# Sheet3.net
KiCad netlist of a schematic drawn in Altium Designer
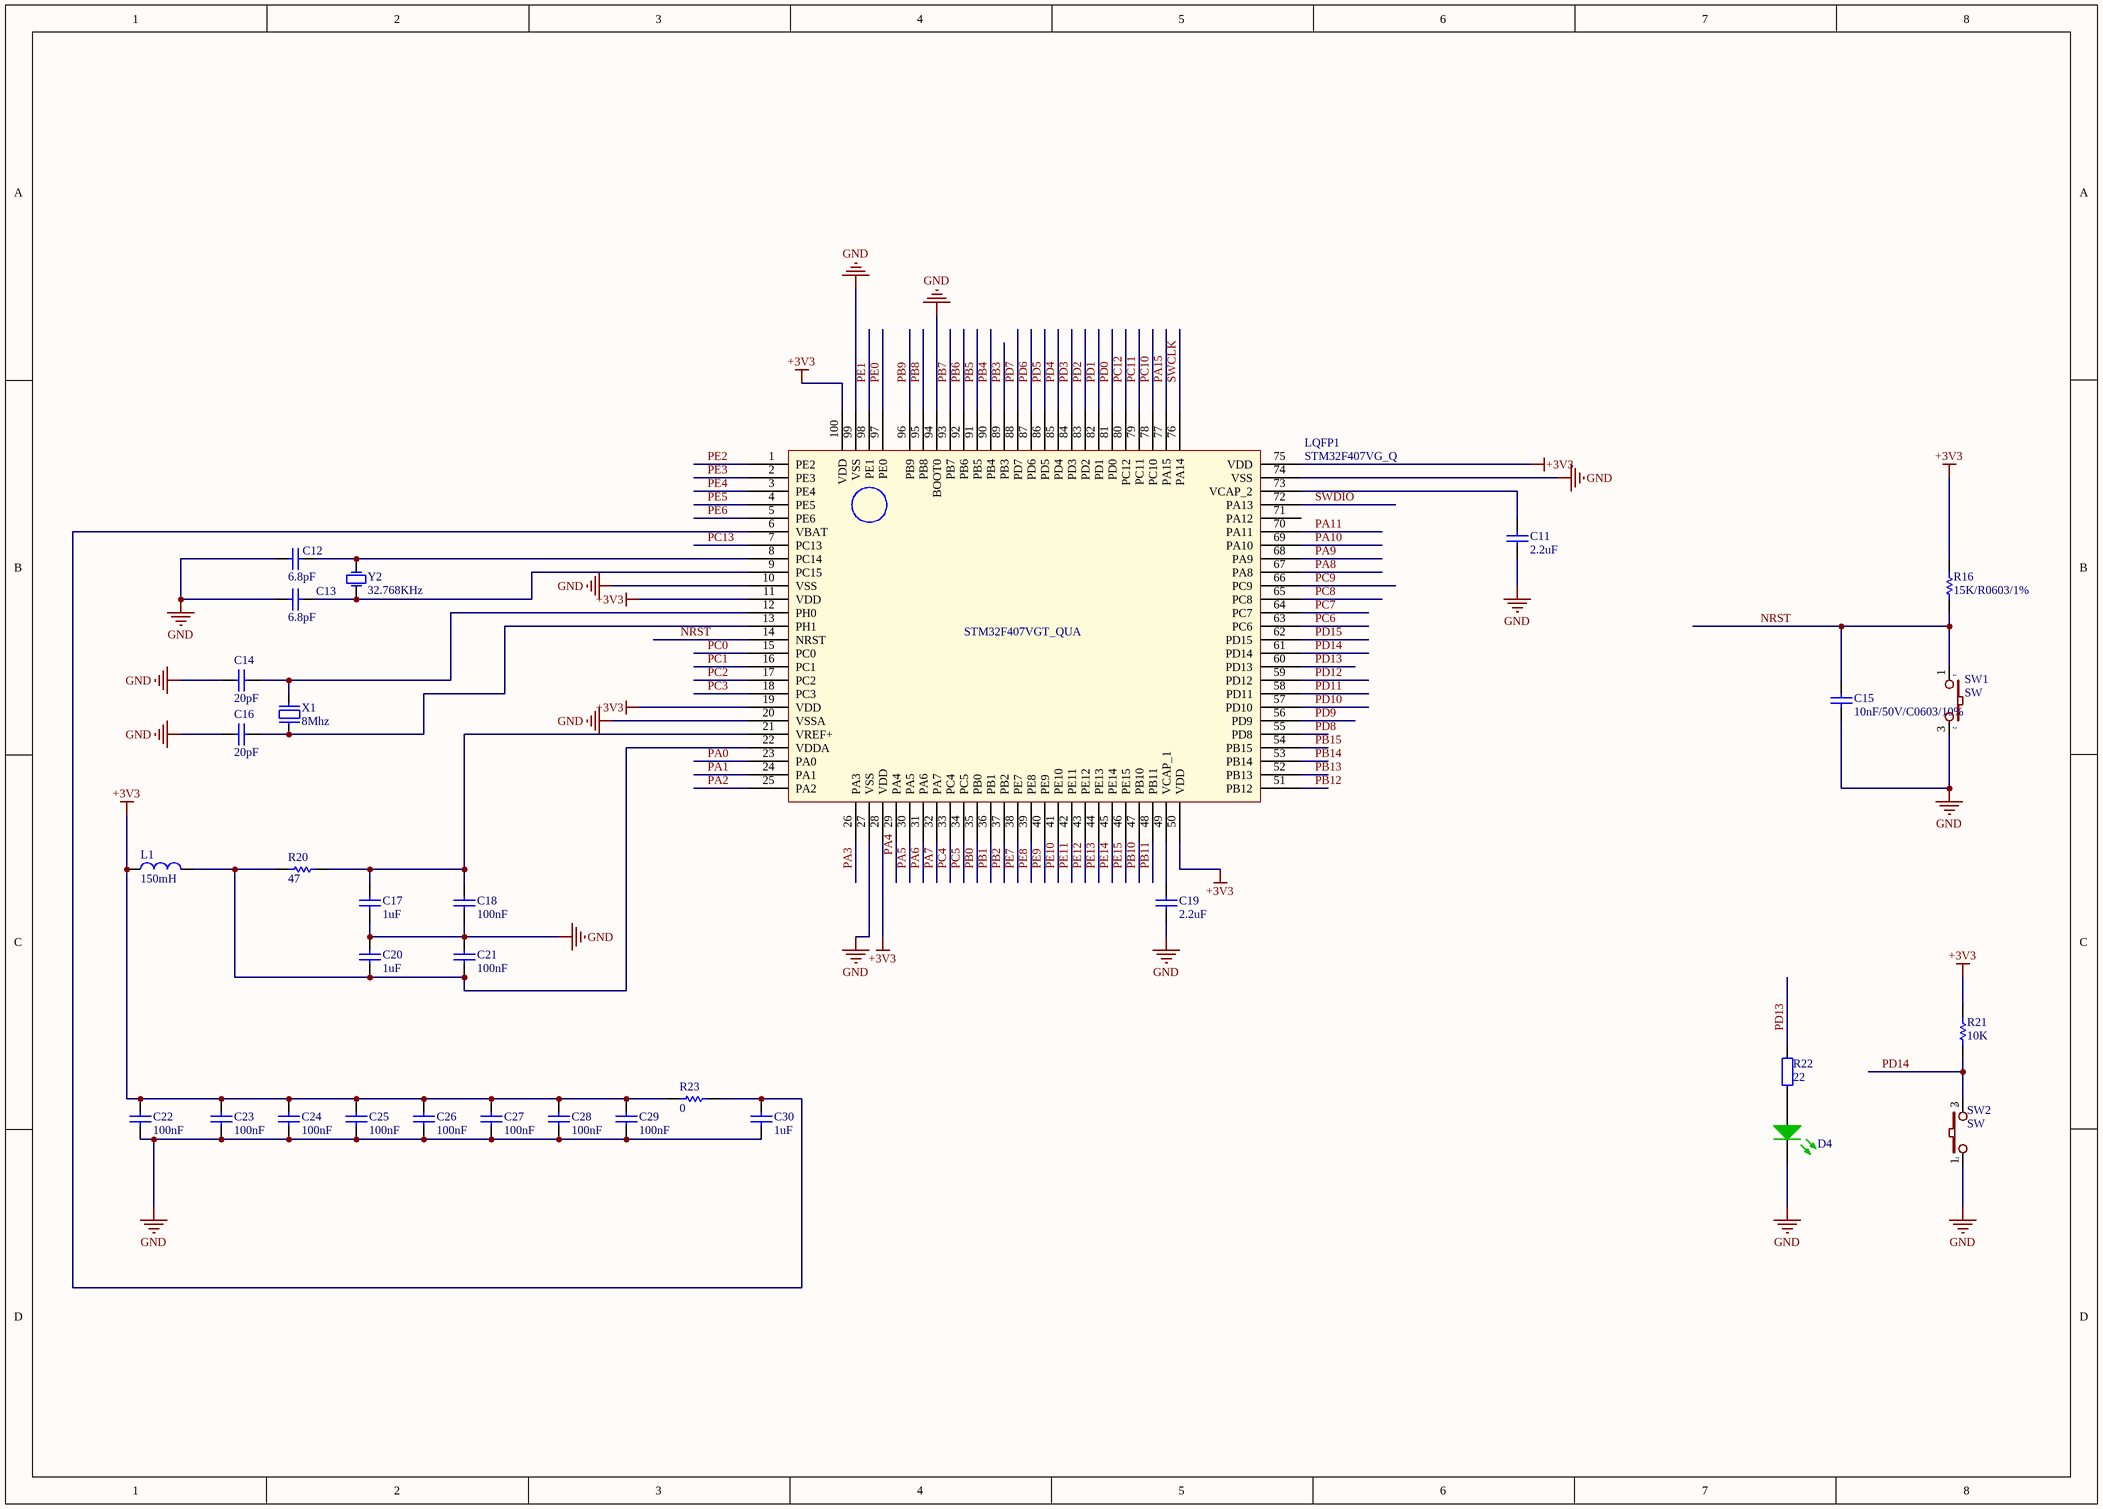
[diagram p0: Sheet3.SchDoc]

(export (version "E")
  (design (tool "Eeschema 10.0.6"))
  (components
    (comp (ref "C11")
      (value "2.2uF")
      (footprint "Cap Ceramic 0805 SMD")
      (description "CAP CER 22PF 50V NP0 0603")
      (fields
        (field (name "MANUFACTURER") "Kemet")
        (field (name "MANUFACTURER PART NUMBER") "C0603C220K5GACTU")
      )
      (libsource (lib "lpson") (part "22pF/50V/C0603/10%"))
    )
    (comp (ref "C12")
      (value "6.8pF")
      (footprint "Cap Ceramic 0805 SMD")
      (description "CAP CER 22PF 50V NP0 0603")
      (fields
        (field (name "MANUFACTURER") "Kemet")
        (field (name "MANUFACTURER PART NUMBER") "C0603C220K5GACTU")
      )
      (libsource (lib "lpson") (part "22pF/50V/C0603/10%"))
    )
    (comp (ref "C13")
      (value "6.8pF")
      (footprint "Cap Ceramic 0805 SMD")
      (description "CAP CER 22PF 50V NP0 0603")
      (fields
        (field (name "MANUFACTURER") "Kemet")
        (field (name "MANUFACTURER PART NUMBER") "C0603C220K5GACTU")
      )
      (libsource (lib "lpson") (part "22pF/50V/C0603/10%"))
    )
    (comp (ref "C14")
      (value "20pF")
      (footprint "Cap Ceramic 0805 SMD")
      (description "CAP CER 22PF 50V NP0 0603")
      (fields
        (field (name "MANUFACTURER") "Kemet")
        (field (name "MANUFACTURER PART NUMBER") "C0603C220K5GACTU")
      )
      (libsource (lib "lpson") (part "22pF/50V/C0603/10%"))
    )
    (comp (ref "C15")
      (value "10nF/50V/C0603/10%")
      (footprint "Cap Ceramic 0805 SMD")
      (description "CAP CER 10000PF 50V X7R 0603")
      (fields
        (field (name "MANUFACTURER") "Murata Electronics North America")
        (field (name "MANUFACTURER PART NUMBER") "GRM188R71H103KA01D")
      )
      (libsource (lib "lpson") (part "10nF/50V/C0603/10%_1"))
    )
    (comp (ref "C16")
      (value "20pF")
      (footprint "Cap Ceramic 0805 SMD")
      (description "CAP CER 22PF 50V NP0 0603")
      (fields
        (field (name "MANUFACTURER") "Kemet")
        (field (name "MANUFACTURER PART NUMBER") "C0603C220K5GACTU")
      )
      (libsource (lib "lpson") (part "22pF/50V/C0603/10%"))
    )
    (comp (ref "C17")
      (value "1uF")
      (footprint "Cap Ceramic 0805 SMD")
      (description "CAP CER 22PF 50V NP0 0603")
      (fields
        (field (name "MANUFACTURER") "Kemet")
        (field (name "MANUFACTURER PART NUMBER") "C0603C220K5GACTU")
      )
      (libsource (lib "lpson") (part "22pF/50V/C0603/10%"))
    )
    (comp (ref "C18")
      (value "100nF")
      (footprint "Cap Ceramic 0805 SMD")
      (description "CAP CER 22PF 50V NP0 0603")
      (fields
        (field (name "MANUFACTURER") "Kemet")
        (field (name "MANUFACTURER PART NUMBER") "C0603C220K5GACTU")
      )
      (libsource (lib "lpson") (part "22pF/50V/C0603/10%"))
    )
    (comp (ref "C19")
      (value "2.2uF")
      (footprint "Cap Ceramic 0805 SMD")
      (description "CAP CER 22PF 50V NP0 0603")
      (fields
        (field (name "MANUFACTURER") "Kemet")
        (field (name "MANUFACTURER PART NUMBER") "C0603C220K5GACTU")
      )
      (libsource (lib "lpson") (part "22pF/50V/C0603/10%"))
    )
    (comp (ref "C20")
      (value "1uF")
      (footprint "Cap Ceramic 0805 SMD")
      (description "CAP CER 22PF 50V NP0 0603")
      (fields
        (field (name "MANUFACTURER") "Kemet")
        (field (name "MANUFACTURER PART NUMBER") "C0603C220K5GACTU")
      )
      (libsource (lib "lpson") (part "22pF/50V/C0603/10%"))
    )
    (comp (ref "C21")
      (value "100nF")
      (footprint "Cap Ceramic 0805 SMD")
      (description "CAP CER 22PF 50V NP0 0603")
      (fields
        (field (name "MANUFACTURER") "Kemet")
        (field (name "MANUFACTURER PART NUMBER") "C0603C220K5GACTU")
      )
      (libsource (lib "lpson") (part "22pF/50V/C0603/10%"))
    )
    (comp (ref "C22")
      (value "100nF")
      (footprint "Cap Ceramic 0805 SMD")
      (description "CAP CER 22PF 50V NP0 0603")
      (fields
        (field (name "MANUFACTURER") "Kemet")
        (field (name "MANUFACTURER PART NUMBER") "C0603C220K5GACTU")
      )
      (libsource (lib "lpson") (part "22pF/50V/C0603/10%"))
    )
    (comp (ref "C23")
      (value "100nF")
      (footprint "Cap Ceramic 0805 SMD")
      (description "CAP CER 22PF 50V NP0 0603")
      (fields
        (field (name "MANUFACTURER") "Kemet")
        (field (name "MANUFACTURER PART NUMBER") "C0603C220K5GACTU")
      )
      (libsource (lib "lpson") (part "22pF/50V/C0603/10%"))
    )
    (comp (ref "C24")
      (value "100nF")
      (footprint "Cap Ceramic 0805 SMD")
      (description "CAP CER 22PF 50V NP0 0603")
      (fields
        (field (name "MANUFACTURER") "Kemet")
        (field (name "MANUFACTURER PART NUMBER") "C0603C220K5GACTU")
      )
      (libsource (lib "lpson") (part "22pF/50V/C0603/10%"))
    )
    (comp (ref "C25")
      (value "100nF")
      (footprint "Cap Ceramic 0805 SMD")
      (description "CAP CER 22PF 50V NP0 0603")
      (fields
        (field (name "MANUFACTURER") "Kemet")
        (field (name "MANUFACTURER PART NUMBER") "C0603C220K5GACTU")
      )
      (libsource (lib "lpson") (part "22pF/50V/C0603/10%"))
    )
    (comp (ref "C26")
      (value "100nF")
      (footprint "Cap Ceramic 0805 SMD")
      (description "CAP CER 22PF 50V NP0 0603")
      (fields
        (field (name "MANUFACTURER") "Kemet")
        (field (name "MANUFACTURER PART NUMBER") "C0603C220K5GACTU")
      )
      (libsource (lib "lpson") (part "22pF/50V/C0603/10%"))
    )
    (comp (ref "C27")
      (value "100nF")
      (footprint "Cap Ceramic 0805 SMD")
      (description "CAP CER 22PF 50V NP0 0603")
      (fields
        (field (name "MANUFACTURER") "Kemet")
        (field (name "MANUFACTURER PART NUMBER") "C0603C220K5GACTU")
      )
      (libsource (lib "lpson") (part "22pF/50V/C0603/10%"))
    )
    (comp (ref "C28")
      (value "100nF")
      (footprint "Cap Ceramic 0805 SMD")
      (description "CAP CER 22PF 50V NP0 0603")
      (fields
        (field (name "MANUFACTURER") "Kemet")
        (field (name "MANUFACTURER PART NUMBER") "C0603C220K5GACTU")
      )
      (libsource (lib "lpson") (part "22pF/50V/C0603/10%"))
    )
    (comp (ref "C29")
      (value "100nF")
      (footprint "Cap Ceramic 0805 SMD")
      (description "CAP CER 22PF 50V NP0 0603")
      (fields
        (field (name "MANUFACTURER") "Kemet")
        (field (name "MANUFACTURER PART NUMBER") "C0603C220K5GACTU")
      )
      (libsource (lib "lpson") (part "22pF/50V/C0603/10%"))
    )
    (comp (ref "C30")
      (value "1uF")
      (footprint "Cap Ceramic 0805 SMD")
      (description "CAP CER 22PF 50V NP0 0603")
      (fields
        (field (name "MANUFACTURER") "Kemet")
        (field (name "MANUFACTURER PART NUMBER") "C0603C220K5GACTU")
      )
      (libsource (lib "lpson") (part "22pF/50V/C0603/10%"))
    )
    (comp (ref "D4")
      (value "GREEN 0603")
      (footprint "Led 0805G")
      (description "LED GREEN CLEAR 0603 SMD")
      (fields
        (field (name "MANUFACTURER") "Lite-On Inc.")
        (field (name "MANUFACTURER PART NUMBER") "LTST-C190KGKT")
      )
      (libsource (lib "STLINKv2DIYmơi") (part "LED GREEN 0603"))
    )
    (comp (ref "L1")
      (value "150mH")
      (footprint "Res 0805 SMD")
      (description "Inductor")
      (libsource (lib "lpson") (part "L1"))
    )
    (comp (ref "LQFP1")
      (value "STM32F407VG_Q")
      (footprint "LPON_IC:STM32F407VG")
      (libsource (lib "SchSTM32F407VGT") (part "STM32F407VG_Q"))
    )
    (comp (ref "R16")
      (value "15K/R0603/1%")
      (footprint "Res 0805 SMD")
      (description "RES SMD 15K OHM 1% 1/10W 0603")
      (fields
        (field (name "MANUFACTURER") "Yageo")
        (field (name "MANUFACTURER PART NUMBER") "RC0603FR-0715KL")
      )
      (libsource (lib "lpson") (part "15K/R0603/1%_1"))
    )
    (comp (ref "R20")
      (value "47")
      (footprint "Res 0805 SMD")
      (description "RES SMD 10K OHM 1% 1/10W 0603")
      (fields
        (field (name "MANUFACTURER") "Yageo")
        (field (name "MANUFACTURER PART NUMBER") "RC0603FR-0710KL")
      )
      (libsource (lib "lpson") (part "10K/R0603/1%"))
    )
    (comp (ref "R21")
      (value "10K")
      (footprint "Res 0805 SMD")
      (description "RES SMD 15K OHM 1% 1/10W 0603")
      (fields
        (field (name "MANUFACTURER") "Yageo")
        (field (name "MANUFACTURER PART NUMBER") "RC0603FR-0715KL")
      )
      (libsource (lib "lpson") (part "15K/R0603/1%_1"))
    )
    (comp (ref "R22")
      (value "22")
      (footprint "Res 0805 SMD")
      (description "Resistor")
      (fields (field (name "Comment") "Res2") (field (name "PUBLISHER") "Altium Limited"))
      (libsource (lib "STLINKv2DIYmơi") (part "Res2"))
    )
    (comp (ref "R23")
      (value "0")
      (footprint "Res 0805 SMD")
      (description "RES SMD 10K OHM 1% 1/10W 0603")
      (fields
        (field (name "MANUFACTURER") "Yageo")
        (field (name "MANUFACTURER PART NUMBER") "RC0603FR-0710KL")
      )
      (libsource (lib "lpson") (part "10K/R0603/1%"))
    )
    (comp (ref "SW1")
      (value "SW")
      (footprint "BUTTON 4 PIN")
      (description "Switch button 2 pin")
      (libsource (lib "lpson") (part "SW2"))
    )
    (comp (ref "SW2")
      (value "SW")
      (footprint "BUTTON 4 PIN")
      (description "Switch button 2 pin")
      (libsource (lib "lpson") (part "SW2"))
    )
    (comp (ref "X1")
      (value "8Mhz")
      (footprint "CRYSTAL")
      (description "Crystal 32,768kHz for timer real")
      (libsource (lib "lpson") (part "XT32k"))
    )
    (comp (ref "Y2")
      (value "32.768KHz")
      (footprint "CR_32768")
      (description "Crystal FC-135R - 32.768KHz")
      (fields (field (name "Comment") "FC-135R - 32.768KHz"))
      (libsource (lib "lpson") (part "FC-135R - 32.768KHz"))
    )
  )
  (nets
    (net (code "1") (name "+3V3") (class "Default")
      (node (ref "C22") (pin "2") (pinfunction "2_2") (pintype "passive"))
      (node (ref "C23") (pin "2") (pinfunction "2_2") (pintype "passive"))
      (node (ref "C24") (pin "2") (pinfunction "2_2") (pintype "passive"))
      (node (ref "C25") (pin "2") (pinfunction "2_2") (pintype "passive"))
      (node (ref "C26") (pin "2") (pinfunction "2_2") (pintype "passive"))
      (node (ref "C27") (pin "2") (pinfunction "2_2") (pintype "passive"))
      (node (ref "C28") (pin "2") (pinfunction "2_2") (pintype "passive"))
      (node (ref "C29") (pin "2") (pinfunction "2_2") (pintype "passive"))
      (node (ref "L1") (pin "1") (pinfunction "1_1") (pintype "passive"))
      (node (ref "LQFP1") (pin "100") (pinfunction "VDD_100") (pintype "passive"))
      (node (ref "LQFP1") (pin "11") (pinfunction "VDD_11") (pintype "passive"))
      (node (ref "LQFP1") (pin "19") (pinfunction "VDD_19") (pintype "passive"))
      (node (ref "LQFP1") (pin "28") (pinfunction "VDD_28") (pintype "passive"))
      (node (ref "LQFP1") (pin "50") (pinfunction "VDD_50") (pintype "passive"))
      (node (ref "LQFP1") (pin "75") (pinfunction "VDD_75") (pintype "passive"))
      (node (ref "R16") (pin "2") (pinfunction "2_2") (pintype "passive"))
      (node (ref "R21") (pin "2") (pinfunction "2_2") (pintype "passive"))
      (node (ref "R23") (pin "2") (pinfunction "2_2") (pintype "passive"))
    )
    (net (code "2") (name "/NRST") (class "Default")
      (node (ref "C15") (pin "2") (pinfunction "2_2") (pintype "passive"))
      (node (ref "LQFP1") (pin "14") (pinfunction "NRST_14") (pintype "passive"))
      (node (ref "R16") (pin "1") (pinfunction "1_1") (pintype "passive"))
      (node (ref "SW1") (pin "1") (pinfunction "1_1") (pintype "passive"))
    )
    (net (code "3") (name "/PA0") (class "Default")
      (node (ref "LQFP1") (pin "23") (pinfunction "PA0_23") (pintype "passive"))
    )
    (net (code "4") (name "/PA1") (class "Default")
      (node (ref "LQFP1") (pin "24") (pinfunction "PA1_24") (pintype "passive"))
    )
    (net (code "5") (name "/PA2") (class "Default")
      (node (ref "LQFP1") (pin "25") (pinfunction "PA2_25") (pintype "passive"))
    )
    (net (code "6") (name "/PA3") (class "Default")
      (node (ref "LQFP1") (pin "26") (pinfunction "PA3_26") (pintype "passive"))
    )
    (net (code "7") (name "/PA4") (class "Default")
      (node (ref "LQFP1") (pin "29") (pinfunction "PA4_29") (pintype "passive"))
    )
    (net (code "8") (name "/PA5") (class "Default")
      (node (ref "LQFP1") (pin "30") (pinfunction "PA5_30") (pintype "passive"))
    )
    (net (code "9") (name "/PA6") (class "Default")
      (node (ref "LQFP1") (pin "31") (pinfunction "PA6_31") (pintype "passive"))
    )
    (net (code "10") (name "/PA7") (class "Default")
      (node (ref "LQFP1") (pin "32") (pinfunction "PA7_32") (pintype "passive"))
    )
    (net (code "11") (name "/PA8") (class "Default")
      (node (ref "LQFP1") (pin "67") (pinfunction "PA8_67") (pintype "passive"))
    )
    (net (code "12") (name "/PA9") (class "Default")
      (node (ref "LQFP1") (pin "68") (pinfunction "PA9_68") (pintype "passive"))
    )
    (net (code "13") (name "/PA10") (class "Default")
      (node (ref "LQFP1") (pin "69") (pinfunction "PA10_69") (pintype "passive"))
    )
    (net (code "14") (name "/PA11") (class "Default")
      (node (ref "LQFP1") (pin "70") (pinfunction "PA11_70") (pintype "passive"))
    )
    (net (code "15") (name "/PA15") (class "Default")
      (node (ref "LQFP1") (pin "77") (pinfunction "PA15_77") (pintype "passive"))
    )
    (net (code "16") (name "/PB0") (class "Default")
      (node (ref "LQFP1") (pin "35") (pinfunction "PB0_35") (pintype "passive"))
    )
    (net (code "17") (name "/PB1") (class "Default")
      (node (ref "LQFP1") (pin "36") (pinfunction "PB1_36") (pintype "passive"))
    )
    (net (code "18") (name "/PB2") (class "Default")
      (node (ref "LQFP1") (pin "37") (pinfunction "PB2_37") (pintype "passive"))
    )
    (net (code "19") (name "/PB3") (class "Default")
      (node (ref "LQFP1") (pin "89") (pinfunction "PB3_89") (pintype "passive"))
    )
    (net (code "20") (name "/PB4") (class "Default")
      (node (ref "LQFP1") (pin "90") (pinfunction "PB4_90") (pintype "passive"))
    )
    (net (code "21") (name "/PB5") (class "Default")
      (node (ref "LQFP1") (pin "91") (pinfunction "PB5_91") (pintype "passive"))
    )
    (net (code "22") (name "/PB6") (class "Default")
      (node (ref "LQFP1") (pin "92") (pinfunction "PB6_92") (pintype "passive"))
    )
    (net (code "23") (name "/PB7") (class "Default")
      (node (ref "LQFP1") (pin "93") (pinfunction "PB7_93") (pintype "passive"))
    )
    (net (code "24") (name "/PB8") (class "Default")
      (node (ref "LQFP1") (pin "95") (pinfunction "PB8_95") (pintype "passive"))
    )
    (net (code "25") (name "/PB9") (class "Default")
      (node (ref "LQFP1") (pin "96") (pinfunction "PB9_96") (pintype "passive"))
    )
    (net (code "26") (name "/PB10") (class "Default")
      (node (ref "LQFP1") (pin "47") (pinfunction "PB10_47") (pintype "passive"))
    )
    (net (code "27") (name "/PB11") (class "Default")
      (node (ref "LQFP1") (pin "48") (pinfunction "PB11_48") (pintype "passive"))
    )
    (net (code "28") (name "/PB12") (class "Default")
      (node (ref "LQFP1") (pin "51") (pinfunction "PB12_51") (pintype "passive"))
    )
    (net (code "29") (name "/PB13") (class "Default")
      (node (ref "LQFP1") (pin "52") (pinfunction "PB13_52") (pintype "passive"))
    )
    (net (code "30") (name "/PB14") (class "Default")
      (node (ref "LQFP1") (pin "53") (pinfunction "PB14_53") (pintype "passive"))
    )
    (net (code "31") (name "/PB15") (class "Default")
      (node (ref "LQFP1") (pin "54") (pinfunction "PB15_54") (pintype "passive"))
    )
    (net (code "32") (name "/PC0") (class "Default")
      (node (ref "LQFP1") (pin "15") (pinfunction "PC0_15") (pintype "passive"))
    )
    (net (code "33") (name "/PC1") (class "Default")
      (node (ref "LQFP1") (pin "16") (pinfunction "PC1_16") (pintype "passive"))
    )
    (net (code "34") (name "/PC2") (class "Default")
      (node (ref "LQFP1") (pin "17") (pinfunction "PC2_17") (pintype "passive"))
    )
    (net (code "35") (name "/PC3") (class "Default")
      (node (ref "LQFP1") (pin "18") (pinfunction "PC3_18") (pintype "passive"))
    )
    (net (code "36") (name "/PC4") (class "Default")
      (node (ref "LQFP1") (pin "33") (pinfunction "PC4_33") (pintype "passive"))
    )
    (net (code "37") (name "/PC5") (class "Default")
      (node (ref "LQFP1") (pin "34") (pinfunction "PC5_34") (pintype "passive"))
    )
    (net (code "38") (name "/PC6") (class "Default")
      (node (ref "LQFP1") (pin "63") (pinfunction "PC6_63") (pintype "passive"))
    )
    (net (code "39") (name "/PC7") (class "Default")
      (node (ref "LQFP1") (pin "64") (pinfunction "PC7_64") (pintype "passive"))
    )
    (net (code "40") (name "/PC8") (class "Default")
      (node (ref "LQFP1") (pin "65") (pinfunction "PC8_65") (pintype "passive"))
    )
    (net (code "41") (name "/PC9") (class "Default")
      (node (ref "LQFP1") (pin "66") (pinfunction "PC9_66") (pintype "passive"))
    )
    (net (code "42") (name "/PC10") (class "Default")
      (node (ref "LQFP1") (pin "78") (pinfunction "PC10_78") (pintype "passive"))
    )
    (net (code "43") (name "/PC11") (class "Default")
      (node (ref "LQFP1") (pin "79") (pinfunction "PC11_79") (pintype "passive"))
    )
    (net (code "44") (name "/PC12") (class "Default")
      (node (ref "LQFP1") (pin "80") (pinfunction "PC12_80") (pintype "passive"))
    )
    (net (code "45") (name "/PC13") (class "Default")
      (node (ref "LQFP1") (pin "7") (pinfunction "PC13_7") (pintype "passive"))
    )
    (net (code "46") (name "/PD0") (class "Default")
      (node (ref "LQFP1") (pin "81") (pinfunction "PD0_81") (pintype "passive"))
    )
    (net (code "47") (name "/PD1") (class "Default")
      (node (ref "LQFP1") (pin "82") (pinfunction "PD1_82") (pintype "passive"))
    )
    (net (code "48") (name "/PD2") (class "Default")
      (node (ref "LQFP1") (pin "83") (pinfunction "PD2_83") (pintype "passive"))
    )
    (net (code "49") (name "/PD3") (class "Default")
      (node (ref "LQFP1") (pin "84") (pinfunction "PD3_84") (pintype "passive"))
    )
    (net (code "50") (name "/PD4") (class "Default")
      (node (ref "LQFP1") (pin "85") (pinfunction "PD4_85") (pintype "passive"))
    )
    (net (code "51") (name "/PD5") (class "Default")
      (node (ref "LQFP1") (pin "86") (pinfunction "PD5_86") (pintype "passive"))
    )
    (net (code "52") (name "/PD6") (class "Default")
      (node (ref "LQFP1") (pin "87") (pinfunction "PD6_87") (pintype "passive"))
    )
    (net (code "53") (name "/PD7") (class "Default")
      (node (ref "LQFP1") (pin "88") (pinfunction "PD7_88") (pintype "passive"))
    )
    (net (code "54") (name "/PD8") (class "Default")
      (node (ref "LQFP1") (pin "55") (pinfunction "PD8_55") (pintype "passive"))
    )
    (net (code "55") (name "/PD9") (class "Default")
      (node (ref "LQFP1") (pin "56") (pinfunction "PD9_56") (pintype "passive"))
    )
    (net (code "56") (name "/PD10") (class "Default")
      (node (ref "LQFP1") (pin "57") (pinfunction "PD10_57") (pintype "passive"))
    )
    (net (code "57") (name "/PD11") (class "Default")
      (node (ref "LQFP1") (pin "58") (pinfunction "PD11_58") (pintype "passive"))
    )
    (net (code "58") (name "/PD12") (class "Default")
      (node (ref "LQFP1") (pin "59") (pinfunction "PD12_59") (pintype "passive"))
    )
    (net (code "59") (name "/PD13") (class "Default")
      (node (ref "LQFP1") (pin "60") (pinfunction "PD13_60") (pintype "passive"))
      (node (ref "R22") (pin "1") (pinfunction "1_1") (pintype "passive"))
    )
    (net (code "60") (name "/PD14") (class "Default")
      (node (ref "LQFP1") (pin "61") (pinfunction "PD14_61") (pintype "passive"))
      (node (ref "R21") (pin "1") (pinfunction "1_1") (pintype "passive"))
      (node (ref "SW2") (pin "3") (pinfunction "3_3") (pintype "passive"))
    )
    (net (code "61") (name "/PD15") (class "Default")
      (node (ref "LQFP1") (pin "62") (pinfunction "PD15_62") (pintype "passive"))
    )
    (net (code "62") (name "/PE0") (class "Default")
      (node (ref "LQFP1") (pin "97") (pinfunction "PE0_97") (pintype "passive"))
    )
    (net (code "63") (name "/PE1") (class "Default")
      (node (ref "LQFP1") (pin "98") (pinfunction "PE1_98") (pintype "passive"))
    )
    (net (code "64") (name "/PE2") (class "Default")
      (node (ref "LQFP1") (pin "1") (pinfunction "PE2_1") (pintype "passive"))
    )
    (net (code "65") (name "/PE3") (class "Default")
      (node (ref "LQFP1") (pin "2") (pinfunction "PE3_2") (pintype "passive"))
    )
    (net (code "66") (name "/PE4") (class "Default")
      (node (ref "LQFP1") (pin "3") (pinfunction "PE4_3") (pintype "passive"))
    )
    (net (code "67") (name "/PE5") (class "Default")
      (node (ref "LQFP1") (pin "4") (pinfunction "PE5_4") (pintype "passive"))
    )
    (net (code "68") (name "/PE6") (class "Default")
      (node (ref "LQFP1") (pin "5") (pinfunction "PE6_5") (pintype "passive"))
    )
    (net (code "69") (name "/PE7") (class "Default")
      (node (ref "LQFP1") (pin "38") (pinfunction "PE7_38") (pintype "passive"))
    )
    (net (code "70") (name "/PE8") (class "Default")
      (node (ref "LQFP1") (pin "39") (pinfunction "PE8_39") (pintype "passive"))
    )
    (net (code "71") (name "/PE9") (class "Default")
      (node (ref "LQFP1") (pin "40") (pinfunction "PE9_40") (pintype "passive"))
    )
    (net (code "72") (name "/PE10") (class "Default")
      (node (ref "LQFP1") (pin "41") (pinfunction "PE10_41") (pintype "passive"))
    )
    (net (code "73") (name "/PE11") (class "Default")
      (node (ref "LQFP1") (pin "42") (pinfunction "PE11_42") (pintype "passive"))
    )
    (net (code "74") (name "/PE12") (class "Default")
      (node (ref "LQFP1") (pin "43") (pinfunction "PE12_43") (pintype "passive"))
    )
    (net (code "75") (name "/PE13") (class "Default")
      (node (ref "LQFP1") (pin "44") (pinfunction "PE13_44") (pintype "passive"))
    )
    (net (code "76") (name "/PE14") (class "Default")
      (node (ref "LQFP1") (pin "45") (pinfunction "PE14_45") (pintype "passive"))
    )
    (net (code "77") (name "/PE15") (class "Default")
      (node (ref "LQFP1") (pin "46") (pinfunction "PE15_46") (pintype "passive"))
    )
    (net (code "78") (name "/SWCLK") (class "Default")
      (node (ref "LQFP1") (pin "76") (pinfunction "PA14_76") (pintype "passive"))
    )
    (net (code "79") (name "/SWDIO") (class "Default")
      (node (ref "LQFP1") (pin "72") (pinfunction "PA13_72") (pintype "passive"))
    )
    (net (code "80") (name "GND") (class "Default")
      (node (ref "C11") (pin "1") (pinfunction "1_1") (pintype "passive"))
      (node (ref "C12") (pin "2") (pinfunction "2_2") (pintype "passive"))
      (node (ref "C13") (pin "2") (pinfunction "2_2") (pintype "passive"))
      (node (ref "C14") (pin "2") (pinfunction "2_2") (pintype "passive"))
      (node (ref "C15") (pin "1") (pinfunction "1_1") (pintype "passive"))
      (node (ref "C16") (pin "2") (pinfunction "2_2") (pintype "passive"))
      (node (ref "C17") (pin "1") (pinfunction "1_1") (pintype "passive"))
      (node (ref "C18") (pin "1") (pinfunction "1_1") (pintype "passive"))
      (node (ref "C19") (pin "1") (pinfunction "1_1") (pintype "passive"))
      (node (ref "C20") (pin "2") (pinfunction "2_2") (pintype "passive"))
      (node (ref "C21") (pin "2") (pinfunction "2_2") (pintype "passive"))
      (node (ref "C22") (pin "1") (pinfunction "1_1") (pintype "passive"))
      (node (ref "C23") (pin "1") (pinfunction "1_1") (pintype "passive"))
      (node (ref "C24") (pin "1") (pinfunction "1_1") (pintype "passive"))
      (node (ref "C25") (pin "1") (pinfunction "1_1") (pintype "passive"))
      (node (ref "C26") (pin "1") (pinfunction "1_1") (pintype "passive"))
      (node (ref "C27") (pin "1") (pinfunction "1_1") (pintype "passive"))
      (node (ref "C28") (pin "1") (pinfunction "1_1") (pintype "passive"))
      (node (ref "C29") (pin "1") (pinfunction "1_1") (pintype "passive"))
      (node (ref "C30") (pin "1") (pinfunction "1_1") (pintype "passive"))
      (node (ref "D4") (pin "2") (pinfunction "K_2") (pintype "passive"))
      (node (ref "LQFP1") (pin "10") (pinfunction "VSS_10") (pintype "passive"))
      (node (ref "LQFP1") (pin "20") (pinfunction "VSSA_20") (pintype "passive"))
      (node (ref "LQFP1") (pin "27") (pinfunction "VSS_27") (pintype "passive"))
      (node (ref "LQFP1") (pin "74") (pinfunction "VSS_74") (pintype "passive"))
      (node (ref "LQFP1") (pin "94") (pinfunction "BOOT0_94") (pintype "passive"))
      (node (ref "LQFP1") (pin "99") (pinfunction "VSS_99") (pintype "passive"))
      (node (ref "SW1") (pin "3") (pinfunction "3_3") (pintype "passive"))
      (node (ref "SW2") (pin "1") (pinfunction "1_1") (pintype "passive"))
    )
    (net (code "81") (name "Net-(D4-A)") (class "Default")
      (node (ref "D4") (pin "1") (pinfunction "A_1") (pintype "passive"))
      (node (ref "R22") (pin "2") (pinfunction "2_2") (pintype "passive"))
    )
    (net (code "82") (name "Net-(LQFP1-PC14)") (class "Default")
      (node (ref "C12") (pin "1") (pinfunction "1_1") (pintype "passive"))
      (node (ref "LQFP1") (pin "8") (pinfunction "PC14_8") (pintype "passive"))
      (node (ref "Y2") (pin "2") (pinfunction "OSC2_2") (pintype "passive"))
    )
    (net (code "83") (name "Net-(LQFP1-PC15)") (class "Default")
      (node (ref "C13") (pin "1") (pinfunction "1_1") (pintype "passive"))
      (node (ref "LQFP1") (pin "9") (pinfunction "PC15_9") (pintype "passive"))
      (node (ref "Y2") (pin "1") (pinfunction "OSC1_1") (pintype "passive"))
    )
    (net (code "84") (name "Net-(LQFP1-PH0)") (class "Default")
      (node (ref "C14") (pin "1") (pinfunction "1_1") (pintype "passive"))
      (node (ref "LQFP1") (pin "12") (pinfunction "PH0_12") (pintype "passive"))
      (node (ref "X1") (pin "2") (pinfunction "2_2") (pintype "passive"))
    )
    (net (code "85") (name "Net-(LQFP1-PH1)") (class "Default")
      (node (ref "C16") (pin "1") (pinfunction "1_1") (pintype "passive"))
      (node (ref "LQFP1") (pin "13") (pinfunction "PH1_13") (pintype "passive"))
      (node (ref "X1") (pin "1") (pinfunction "1_1") (pintype "passive"))
    )
    (net (code "86") (name "Net-(LQFP1-VBAT)") (class "Default")
      (node (ref "C30") (pin "2") (pinfunction "2_2") (pintype "passive"))
      (node (ref "LQFP1") (pin "6") (pinfunction "VBAT_6") (pintype "passive"))
      (node (ref "R23") (pin "1") (pinfunction "1_1") (pintype "passive"))
    )
    (net (code "87") (name "Net-(LQFP1-VCAP_1)") (class "Default")
      (node (ref "C19") (pin "2") (pinfunction "2_2") (pintype "passive"))
      (node (ref "LQFP1") (pin "49") (pinfunction "VCAP_1_49") (pintype "passive"))
    )
    (net (code "88") (name "Net-(LQFP1-VCAP_2)") (class "Default")
      (node (ref "C11") (pin "2") (pinfunction "2_2") (pintype "passive"))
      (node (ref "LQFP1") (pin "73") (pinfunction "VCAP_2_73") (pintype "passive"))
    )
    (net (code "89") (name "Net-(LQFP1-VDDA)") (class "Default")
      (node (ref "C20") (pin "1") (pinfunction "1_1") (pintype "passive"))
      (node (ref "C21") (pin "1") (pinfunction "1_1") (pintype "passive"))
      (node (ref "L1") (pin "2") (pinfunction "2_2") (pintype "passive"))
      (node (ref "LQFP1") (pin "22") (pinfunction "VDDA_22") (pintype "passive"))
      (node (ref "R20") (pin "2") (pinfunction "2_2") (pintype "passive"))
    )
    (net (code "90") (name "Net-(LQFP1-VREF+)") (class "Default")
      (node (ref "C17") (pin "2") (pinfunction "2_2") (pintype "passive"))
      (node (ref "C18") (pin "2") (pinfunction "2_2") (pintype "passive"))
      (node (ref "LQFP1") (pin "21") (pinfunction "VREF+_21") (pintype "passive"))
      (node (ref "R20") (pin "1") (pinfunction "1_1") (pintype "passive"))
    )
    (net (code "91") (name "unconnected-(LQFP1-PA12-Pad71)") (class "Default")
      (node (ref "LQFP1") (pin "71") (pinfunction "PA12_71") (pintype "passive"))
    )
  )
)
